# EPS_MPPT_X_EMI-Filter_In.net
KiCad netlist of a schematic drawn in Altium Designer
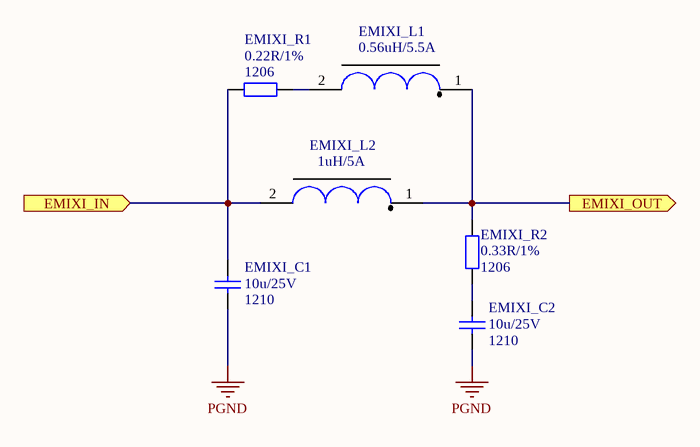
[diagram p0: EPS_MPPT_X_EMI-Filter_In.SchDoc]

(export (version "E")
  (design (tool "Eeschema 10.0.6"))
  (components
    (comp (ref "EMIXI_C1")
      (value "10u/25V")
      (footprint "SMD_Capacitor_1210")
      (description "Ceramic Cap Murata Automotive 10u/25V X7R 1210")
      (fields
        (field (name "MANUFACTURER") "Murata")
        (field (name "MANUFACTURERPARTNUMBER") "GCJ32ER71E106KA12L")
        (field (name "PACKAGE") "1210")
      )
      (libsource (lib "capacitors") (part "Cer_GCJ32ER71E106KA12L"))
    )
    (comp (ref "EMIXI_C2")
      (value "10u/25V")
      (footprint "SMD_Capacitor_1210")
      (description "Ceramic Cap Murata Automotive 10u/25V X7R 1210")
      (fields
        (field (name "MANUFACTURER") "Murata")
        (field (name "MANUFACTURERPARTNUMBER") "GCJ32ER71E106KA12L")
        (field (name "PACKAGE") "1210")
      )
      (libsource (lib "capacitors") (part "Cer_GCJ32ER71E106KA12L"))
    )
    (comp (ref "EMIXI_L1")
      (value "0.56uH/5.5A")
      (footprint "Vishay_IHLP1212")
      (description "Vishay IHLP1212 Inductor, L=0.56uH, Irise40deg=5.5A, ESR=16mR, SRF=1MHz.")
      (fields
        (field (name "MANUFACTURER") "Vishay")
        (field (name "MANUFACTURERPARTNUMBER") "IHLP1212BZERR56M11")
      )
      (libsource (lib "inductors") (part "IHLP1212BZERR56M11"))
    )
    (comp (ref "EMIXI_L2")
      (value "1uH/5A")
      (footprint "Vishay_IHLP1212")
      (description "Vishay IHLP1212 Inductor, L=1uH, Irise40deg=5A, ESR=20mR, SRF=1MHz.")
      (fields
        (field (name "MANUFACTURER") "Vishay")
        (field (name "MANUFACTURERPARTNUMBER") "IHLP1212BZER1R0M11")
      )
      (libsource (lib "inductors") (part "IHLP1212BZER1R0M11"))
    )
    (comp (ref "EMIXI_R1")
      (value "0.22R/1%")
      (footprint "SMD_Resistor_1206")
      (description "Panasonic Resistor 0.22R 1% 1206 330mW")
      (fields
        (field (name "MANUFACTURER") "Panasonic")
        (field (name "MANUFACTURERPARTNUMBER") "ERJ-8BQFR22V")
        (field (name "PACKAGE") "1206")
      )
      (libsource (lib "resistors") (part "ERJ-8BQFR22V"))
    )
    (comp (ref "EMIXI_R2")
      (value "0.33R/1%")
      (footprint "SMD_Resistor_1206")
      (description "Panasonic Resistor 0.33R 1% 1206 330mW")
      (fields
        (field (name "MANUFACTURER") "Panasonic")
        (field (name "MANUFACTURERPARTNUMBER") "ERJ-8BQFR33V")
        (field (name "PACKAGE") "1206")
      )
      (libsource (lib "resistors") (part "ERJ-8BQFR33V"))
    )
  )
  (nets
    (net (code "1") (name "/EMIXI_IN") (class "Default")
      (node (ref "EMIXI_C1") (pin "1") (pinfunction "1_1") (pintype "passive"))
      (node (ref "EMIXI_L2") (pin "2") (pinfunction "2_2") (pintype "passive"))
      (node (ref "EMIXI_R1") (pin "1") (pinfunction "1_1") (pintype "passive"))
    )
    (net (code "2") (name "/EMIXI_OUT") (class "Default")
      (node (ref "EMIXI_L1") (pin "1") (pinfunction "1_1") (pintype "passive"))
      (node (ref "EMIXI_L2") (pin "1") (pinfunction "1_1") (pintype "passive"))
      (node (ref "EMIXI_R2") (pin "2") (pinfunction "2_2") (pintype "passive"))
    )
    (net (code "3") (name "Net-(EMIXI_C2-Pad1)") (class "Default")
      (node (ref "EMIXI_C2") (pin "1") (pinfunction "1_1") (pintype "passive"))
      (node (ref "EMIXI_R2") (pin "1") (pinfunction "1_1") (pintype "passive"))
    )
    (net (code "4") (name "Net-(EMIXI_L1-Pad2)") (class "Default")
      (node (ref "EMIXI_L1") (pin "2") (pinfunction "2_2") (pintype "passive"))
      (node (ref "EMIXI_R1") (pin "2") (pinfunction "2_2") (pintype "passive"))
    )
    (net (code "5") (name "PGND") (class "Default")
      (node (ref "EMIXI_C1") (pin "2") (pinfunction "2_2") (pintype "passive"))
      (node (ref "EMIXI_C2") (pin "2") (pinfunction "2_2") (pintype "passive"))
    )
  )
)
